# POWER.net
KiCad netlist of a schematic drawn in Altium Designer
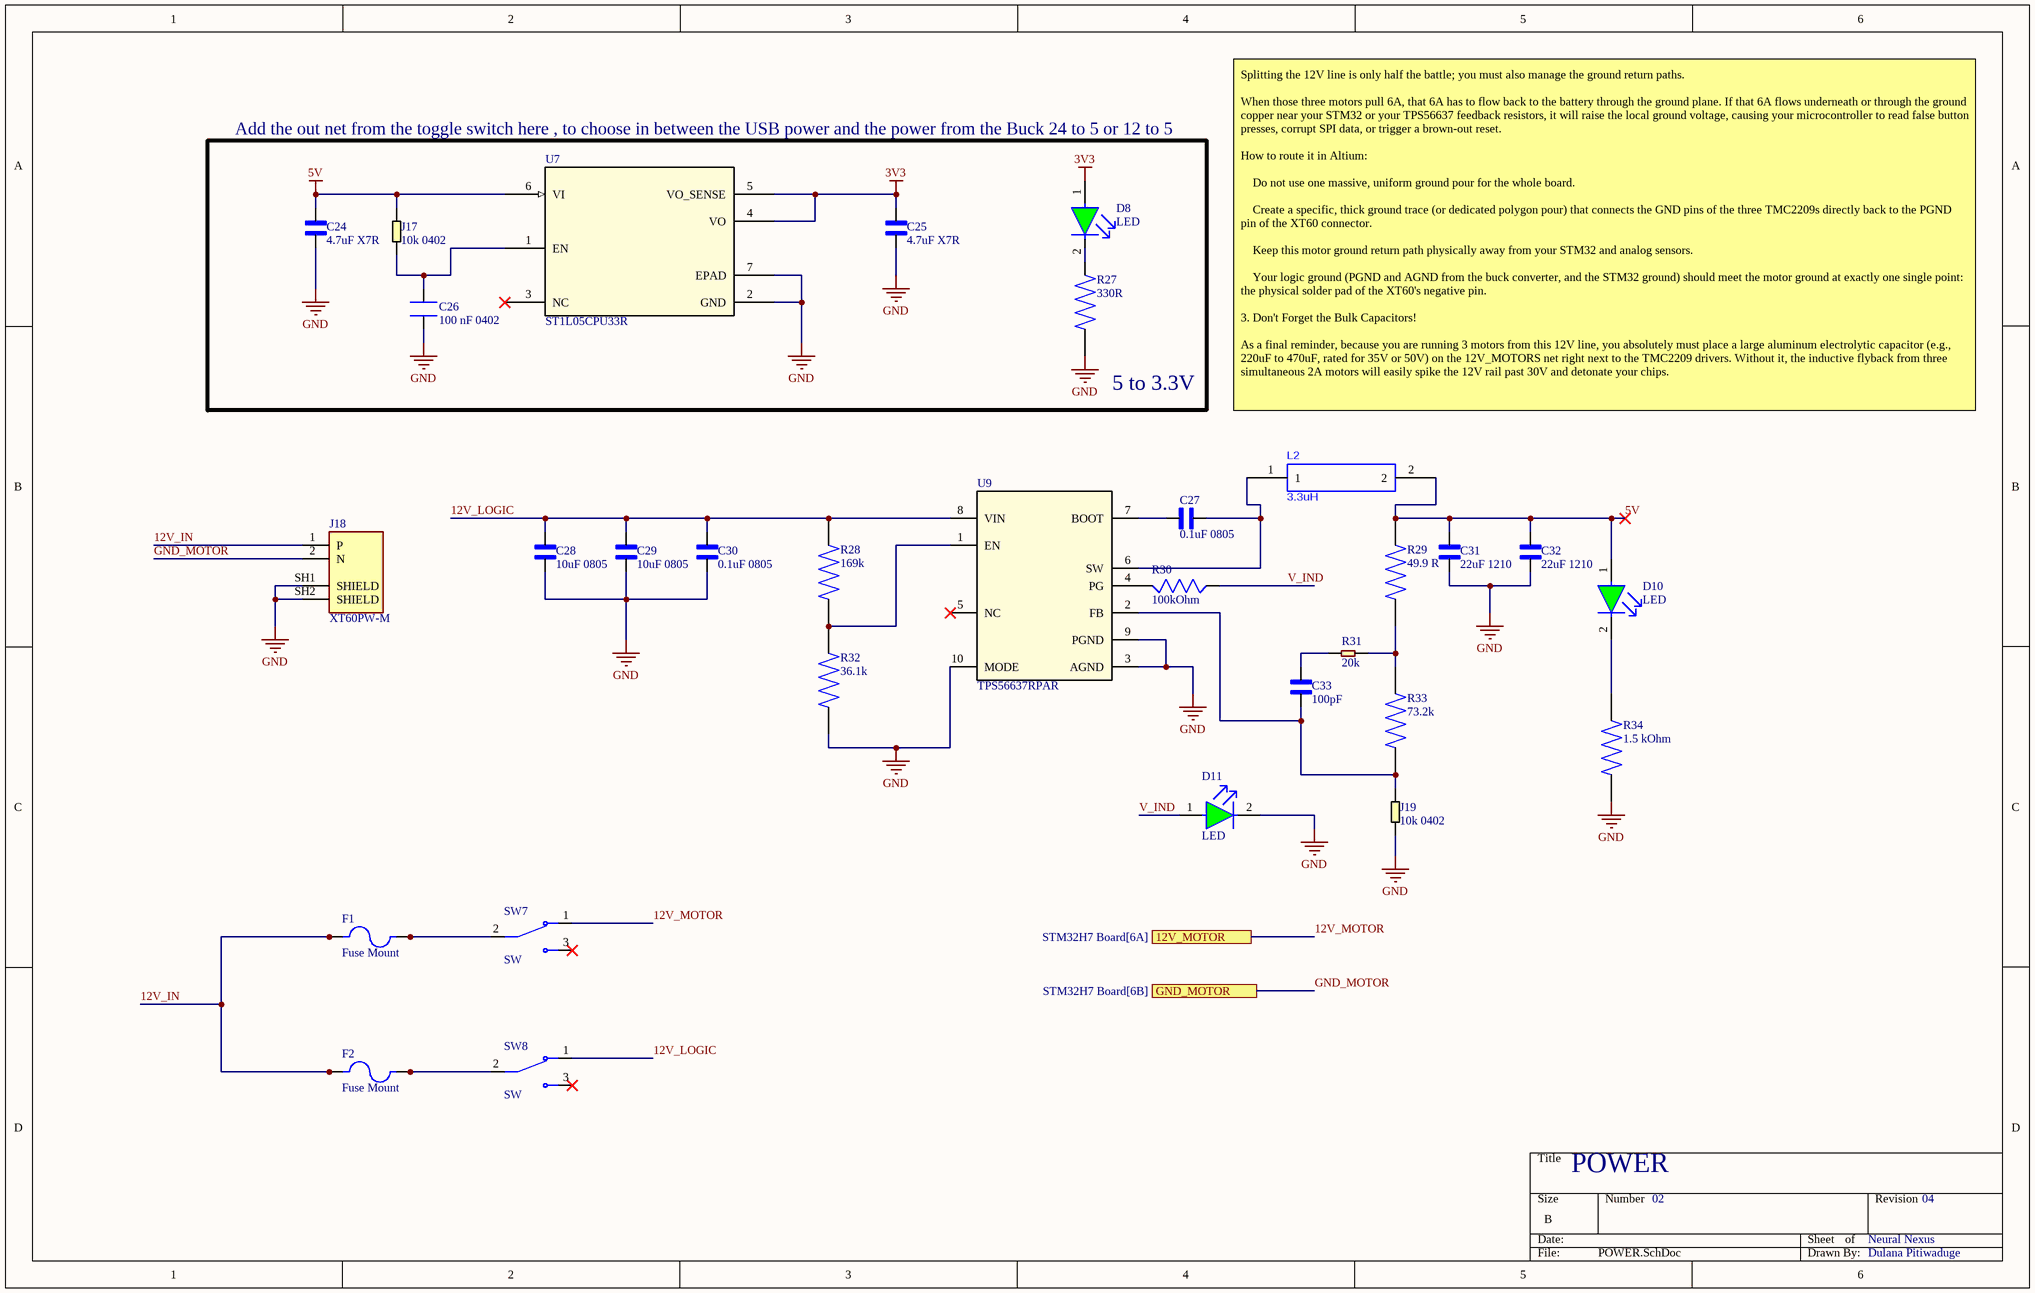
[diagram p0: POWER.SchDoc]

(export (version "E")
  (design (tool "Eeschema 10.0.6"))
  (components
    (comp (ref "C24")
      (value "4.7uF X7R")
      (footprint "CAPC2012X145N")
      (description "C Series 0805 4.7 uF 10 V Â±10% Tolerance X7R SMT Multilayer Ceramic Capacitor")
      (fields (field (name "MF") "TDK") (field (name "MP") "C2012X7R1A475K125AC"))
      (libsource (lib "Schlib1") (part "C2012X7R1A475K125AC"))
    )
    (comp (ref "C25")
      (value "4.7uF X7R")
      (footprint "CAPC2012X145N")
      (description "C Series 0805 4.7 uF 10 V Â±10% Tolerance X7R SMT Multilayer Ceramic Capacitor")
      (fields (field (name "MF") "TDK") (field (name "MP") "C2012X7R1A475K125AC"))
      (libsource (lib "Schlib1") (part "C2012X7R1A475K125AC"))
    )
    (comp (ref "C26")
      (value "100 nF 0402")
      (footprint "CAPC1005X55N")
      (description "0.1 ÂµF Â±10% 10V Ceramic Capacitor X7R 0402 (1005 Metric)")
      (fields (field (name "MF") "Samsung Electro-Mechanics") (field (name "MP") "CL05B104KP5NNNC"))
      (libsource (lib "EDR") (part "CL05B104KP5NNNC"))
    )
    (comp (ref "C27")
      (value "0.1uF 0805")
      (footprint "CAPC2012X95N")
      (description "0.1 ÂµF Â±10% 50V Ceramic Capacitor X7R 0805 (2012 Metric)")
      (fields (field (name "MF") "Samsung Electro-Mechanics") (field (name "MP") "CL21B104KBCNNNC"))
      (libsource (lib "Schlib1") (part "CL21B104KBCNNNC"))
    )
    (comp (ref "C28")
      (value "10uF 0805")
      (footprint "CAPC2012X145N")
      (description "SMD capacitor X7R(MURATA) with capacitance 10uF Tol.10%. Rated voltage 25Vdc 125C")
      (fields (field (name "MF") "Murata") (field (name "MP") "GRM21BZ71E106KE15L"))
      (libsource (lib "Schlib1") (part "GRM21BZ71E106KE15L"))
    )
    (comp (ref "C29")
      (value "10uF 0805")
      (footprint "CAPC2012X145N")
      (description "SMD capacitor X7R(MURATA) with capacitance 10uF Tol.10%. Rated voltage 25Vdc 125C")
      (fields (field (name "MF") "Murata") (field (name "MP") "GRM21BZ71E106KE15L"))
      (libsource (lib "Schlib1") (part "GRM21BZ71E106KE15L"))
    )
    (comp (ref "C30")
      (value "0.1uF 0805")
      (footprint "CAPC2012X95N")
      (description "0.1 ÂµF Â±10% 50V Ceramic Capacitor X7R 0805 (2012 Metric)")
      (fields (field (name "MF") "Samsung Electro-Mechanics") (field (name "MP") "CL21B104KBCNNNC"))
      (libsource (lib "") (part "CL21B104KBCNNNC_1"))
    )
    (comp (ref "C31")
      (value "22uF 1210")
      (footprint "CAPC3225X270N")
      (description "SMD capacitor X7R(EIA) with capacitance 22uF Tol.10%. Rated voltage 25Vdc 125C")
      (fields (field (name "MF") "Murata Electronics") (field (name "MP") "GRM32ER71E226KE15L"))
      (libsource (lib "Schlib1") (part "GRM32ER71E226KE15L"))
    )
    (comp (ref "C32")
      (value "22uF 1210")
      (footprint "CAPC3225X270N")
      (description "SMD capacitor X7R(EIA) with capacitance 22uF Tol.10%. Rated voltage 25Vdc 125C")
      (fields (field (name "MF") "Murata Electronics") (field (name "MP") "GRM32ER71E226KE15L"))
      (libsource (lib "Schlib1") (part "GRM32ER71E226KE15L"))
    )
    (comp (ref "C33")
      (value "100pF")
      (footprint "CAPC1005X55N")
      (description "100 pF Â±5% 50V Ceramic Capacitor C0G, NP0 0402 (1005 Metric)")
      (fields (field (name "MF") "Samsung Electro-Mechanics") (field (name "MP") "CL05C101JB5NNNC"))
      (libsource (lib "EDR") (part "CL05C101JB5NNNC"))
    )
    (comp (ref "D8")
      (value "LED")
      (footprint "FP-SML-LX0805SRC-TR-MFG")
      (description "LED RED CLEAR SMD")
      (fields (field (name "TRONIC PART NO") "LE0011"))
      (libsource (lib "EDR") (part "RED GREEN"))
    )
    (comp (ref "D10")
      (value "LED")
      (footprint "FP-SML-LX0805SRC-TR-MFG")
      (description "LED RED CLEAR SMD")
      (fields (field (name "TRONIC PART NO") "LE0011"))
      (libsource (lib "EDR") (part "RED GREEN"))
    )
    (comp (ref "D11")
      (value "LED")
      (footprint "FP-SML-LX0805SRC-TR-MFG")
      (description "LED RED CLEAR SMD")
      (fields (field (name "TRONIC PART NO") "LE0011"))
      (libsource (lib "EDR") (part "RED GREEN"))
    )
    (comp (ref "F1")
      (value "Fuse Mount")
      (footprint "FUSE_3568")
      (fields (field (name "MF") "Keystone Electronics") (field (name "MP") "3568"))
      (libsource (lib "EDR") (part "Fuse Mount"))
    )
    (comp (ref "F2")
      (value "Fuse Mount")
      (footprint "FUSE_3568")
      (fields (field (name "MF") "Keystone Electronics") (field (name "MP") "3568"))
      (libsource (lib "EDR") (part "Fuse Mount"))
    )
    (comp (ref "J17")
      (value "10k 0402")
      (footprint "RESC1005X40N")
      (description "301010004")
      (fields (field (name "MF") "{'manufacturer': u'YAGEO'}") (field (name "MP") "RC0402JR-0710KL"))
      (libsource (lib "EDR") (part "SMD-RES-10K-5%-1/(0402)"))
    )
    (comp (ref "J18")
      (value "XT60PW-M")
      (footprint "AMASS_XT60PW-M")
      (description "Socket, DC supply, male, PIN: 2")
      (fields (field (name "MF") "AMASS") (field (name "LCSC PART NUMBER") "C98732"))
      (libsource (lib "EDR") (part "XT60PW-M"))
    )
    (comp (ref "J19")
      (value "10k 0402")
      (footprint "RESC1005X40N")
      (description "301010004")
      (fields (field (name "MF") "{'manufacturer': u'YAGEO'}") (field (name "MP") "RC0402JR-0710KL"))
      (libsource (lib "EDR") (part "SMD-RES-10K-5%-1/(0402)"))
    )
    (comp (ref "L2")
      (value "3.3uH")
      (footprint "IND-SMD_L4.0-W4.0 - duplicate")
      (description "FHD4020S-3R3MT")
      (fields (field (name "TRONIC PART NO") "IN0008"))
      (libsource (lib "EDR") (part "33uH"))
    )
    (comp (ref "R27")
      (value "330R")
      (footprint "RESC1005X40N")
      (description "330 Ohms Â±1% 0.063W, 1/16W Chip Resistor 0402 (1005 Metric) Moisture Resistant Thick Film")
      (fields (field (name "MF") "Yageo") (field (name "MP") "RC0402FR-07330RL"))
      (libsource (lib "EDR") (part "RC0402FR-07330RL"))
    )
    (comp (ref "R28")
      (value "169k")
      (footprint "RESC1508X55N")
      (description "169 kOhms Â±1% 0.1W, 1/10W Chip Resistor 0603 (1608 Metric) Automotive AEC-Q200 Thick Film")
      (fields (field (name "MF") "Stackpole Electronics Inc") (field (name "MP") "RMCF0603FT169K"))
      (libsource (lib "EDR") (part "RMCF0603FT169K"))
    )
    (comp (ref "R29")
      (value "49.9 R")
      (footprint "RESC1005X40N")
      (fields (field (name "MF") "Vishay Dale") (field (name "MP") "CRCW040249R9FKED"))
      (libsource (lib "EDR") (part "CRCW040249R9FKED"))
    )
    (comp (ref "R30")
      (value "100kOhm")
      (footprint "RESC1005X40")
      (description "100 kOhms Â±1% 0.063W, 1/16W Chip Resistor 0402 (1005 Metric) Moisture Resistant Thick Film")
      (fields (field (name "MF") "Yageo") (field (name "MP") "RC0402FR-07100KL"))
      (libsource (lib "EDR") (part "RC0402FR-07100KL"))
    )
    (comp (ref "R31")
      (value "20k")
      (footprint "R0603")
      (description "20 kOhms Â±1% 0.1W, 1/10W Chip Resistor 0603 (1608 Metric) Moisture Resistant Thick Film")
      (fields (field (name "MF") "Yageo") (field (name "MP") "RC0603FR-0720KL"))
      (libsource (lib "EDR") (part "SMD-RES-20K-1%-1/10W(0603)"))
    )
    (comp (ref "R32")
      (value "36.1k")
      (footprint "RESC1608X55N")
      (description "RES SMD 36.1KOHM 0.1% 1/10W 0603")
      (fields (field (name "MF") "{'manufacturer': u'YAGEO'}") (field (name "MP") "RT0603BRD0736K1L"))
      (libsource (lib "EDR") (part "RT0603BRD0736K1L"))
    )
    (comp (ref "R33")
      (value "73.2k")
      (footprint "RESC1005X35N")
      (description "RES 73.2K OHM 1% 1/16W 0402")
      (fields (field (name "MP") "RMCF0402FT73K2"))
      (libsource (lib "EDR") (part "RMCF0402FT73K2"))
    )
    (comp (ref "R34")
      (value "1.5 kOhm")
      (footprint "RESC1005X40N")
      (description "1.5 kOhms Â±1% 0.063W, 1/16W Chip Resistor 0402 (1005 Metric) Moisture Resistant Thick Film")
      (fields (field (name "MF") "Yageo") (field (name "MP") "RC0402FR-071K5L"))
      (libsource (lib "EDR") (part "RC0402FR-071K5L"))
    )
    (comp (ref "SW7")
      (value "SW")
      (footprint "SW_100SP3T1B1M2QE")
      (description "TOGGLE, 5A, 120VAC/28VDC SPDT, On-Off-On, Panel Mount, Through Hole")
      (fields (field (name "MF") "E-Switch") (field (name "MP") "100SP3T1B1M2QE"))
      (libsource (lib "EDR") (part "100SP3T1B1M2QE"))
    )
    (comp (ref "SW8")
      (value "SW")
      (footprint "SW_100SP3T1B1M2QE")
      (description "TOGGLE, 5A, 120VAC/28VDC SPDT, On-Off-On, Panel Mount, Through Hole")
      (fields (field (name "MF") "E-Switch") (field (name "MP") "100SP3T1B1M2QE"))
      (libsource (lib "EDR") (part "100SP3T1B1M2QE"))
    )
    (comp (ref "U7")
      (value "ST1L05CPU33R")
      (footprint "DFN6_3X3_STM")
      (description "Very low quiescent BiCMOS voltage regulator")
      (fields (field (name "COPYRIGHT") "Copyright (C) 2026 Ultra Librarian. All rights reserved."))
      (libsource (lib "Schlib1") (part "ST1L05CPU33R"))
    )
    (comp (ref "U9")
      (value "TPS56637RPAR")
      (footprint "CONV_TPS56637RPAR")
      (description "4.5-V to 28-V, 6-A synchronous buck converter with ULQ-Mode 10-VQFN-HR -40 to 150")
      (fields (field (name "COPYRIGHT") "Copyright (C) 2026 Ultra Librarian. All rights reserved."))
      (libsource (lib "Schlib1") (part "TPS56637RPAR"))
    )
  )
  (nets
    (net (code "1") (name "/12V_IN") (class "Default")
      (node (ref "F1") (pin "1") (pinfunction "1_1") (pintype "passive"))
      (node (ref "F1") (pin "3") (pinfunction "1_3") (pintype "passive"))
      (node (ref "F2") (pin "1") (pinfunction "1_1") (pintype "passive"))
      (node (ref "F2") (pin "3") (pinfunction "1_3") (pintype "passive"))
      (node (ref "J18") (pin "1") (pinfunction "P_1") (pintype "passive"))
    )
    (net (code "2") (name "/12V_LOGIC") (class "Default")
      (node (ref "C28") (pin "2") (pinfunction "2_2") (pintype "passive"))
      (node (ref "C29") (pin "2") (pinfunction "2_2") (pintype "passive"))
      (node (ref "C30") (pin "2") (pinfunction "2_2") (pintype "passive"))
      (node (ref "R28") (pin "2") (pinfunction "2_2") (pintype "passive"))
      (node (ref "SW8") (pin "1") (pinfunction "1_1") (pintype "passive"))
      (node (ref "U9") (pin "8") (pinfunction "VIN_8") (pintype "power_in"))
    )
    (net (code "3") (name "/12V_MOTOR") (class "Default")
      (node (ref "SW7") (pin "1") (pinfunction "1_1") (pintype "passive"))
    )
    (net (code "4") (name "/GND_MOTOR") (class "Default")
      (node (ref "J18") (pin "2") (pinfunction "N_2") (pintype "passive"))
    )
    (net (code "5") (name "/V_IND") (class "Default")
      (node (ref "D11") (pin "1") (pinfunction "A_1") (pintype "passive"))
      (node (ref "R30") (pin "2") (pinfunction "2_2") (pintype "passive"))
    )
    (net (code "6") (name "3V3") (class "Default")
      (node (ref "C25") (pin "2") (pinfunction "2_2") (pintype "passive"))
      (node (ref "D8") (pin "1") (pinfunction "A_1") (pintype "passive"))
      (node (ref "U7") (pin "4") (pinfunction "VO_4") (pintype "passive"))
      (node (ref "U7") (pin "5") (pinfunction "VO_SENSE_5") (pintype "passive"))
    )
    (net (code "7") (name "5V") (class "Default")
      (node (ref "C24") (pin "2") (pinfunction "2_2") (pintype "passive"))
      (node (ref "C31") (pin "2") (pinfunction "2_2") (pintype "passive"))
      (node (ref "C32") (pin "2") (pinfunction "2_2") (pintype "passive"))
      (node (ref "D10") (pin "1") (pinfunction "A_1") (pintype "passive"))
      (node (ref "J17") (pin "2") (pinfunction "2_2") (pintype "passive"))
      (node (ref "L2") (pin "2") (pinfunction "2_2") (pintype "passive"))
      (node (ref "R29") (pin "2") (pinfunction "2_2") (pintype "passive"))
      (node (ref "U7") (pin "6") (pinfunction "VI_6") (pintype "input"))
    )
    (net (code "8") (name "GND") (class "Default")
      (node (ref "C24") (pin "1") (pinfunction "1_1") (pintype "passive"))
      (node (ref "C25") (pin "1") (pinfunction "1_1") (pintype "passive"))
      (node (ref "C26") (pin "1") (pinfunction "1_1") (pintype "passive"))
      (node (ref "C28") (pin "1") (pinfunction "1_1") (pintype "passive"))
      (node (ref "C29") (pin "1") (pinfunction "1_1") (pintype "passive"))
      (node (ref "C30") (pin "1") (pinfunction "1_1") (pintype "passive"))
      (node (ref "C31") (pin "1") (pinfunction "1_1") (pintype "passive"))
      (node (ref "C32") (pin "1") (pinfunction "1_1") (pintype "passive"))
      (node (ref "D11") (pin "2") (pinfunction "C_2") (pintype "passive"))
      (node (ref "J18") (pin "SH1") (pinfunction "SHIELD_SH1") (pintype "passive"))
      (node (ref "J18") (pin "SH2") (pinfunction "SHIELD_SH2") (pintype "passive"))
      (node (ref "J19") (pin "1") (pinfunction "1_1") (pintype "passive"))
      (node (ref "R27") (pin "1") (pinfunction "1_1") (pintype "passive"))
      (node (ref "R32") (pin "1") (pinfunction "1_1") (pintype "passive"))
      (node (ref "R34") (pin "1") (pinfunction "1_1") (pintype "passive"))
      (node (ref "U7") (pin "2") (pinfunction "GND_2") (pintype "power_in"))
      (node (ref "U7") (pin "7") (pinfunction "EPAD_7") (pintype "passive"))
      (node (ref "U9") (pin "10") (pinfunction "MODE_10") (pintype "power_in"))
      (node (ref "U9") (pin "3") (pinfunction "AGND_3") (pintype "power_in"))
      (node (ref "U9") (pin "9") (pinfunction "PGND_9") (pintype "power_in"))
    )
    (net (code "9") (name "Net-(C33-Pad2)") (class "Default")
      (node (ref "C33") (pin "2") (pinfunction "2_2") (pintype "passive"))
      (node (ref "R31") (pin "1") (pinfunction "1_1") (pintype "passive"))
    )
    (net (code "10") (name "Net-(D8-C)") (class "Default")
      (node (ref "D8") (pin "2") (pinfunction "C_2") (pintype "passive"))
      (node (ref "R27") (pin "2") (pinfunction "2_2") (pintype "passive"))
    )
    (net (code "11") (name "Net-(D10-C)") (class "Default")
      (node (ref "D10") (pin "2") (pinfunction "C_2") (pintype "passive"))
      (node (ref "R34") (pin "2") (pinfunction "2_2") (pintype "passive"))
    )
    (net (code "12") (name "Net-(F1-2-Pad4)") (class "Default")
      (node (ref "F1") (pin "2") (pinfunction "2_2") (pintype "passive"))
      (node (ref "F1") (pin "4") (pinfunction "2_4") (pintype "passive"))
      (node (ref "SW7") (pin "2") (pinfunction "2_2") (pintype "passive"))
    )
    (net (code "13") (name "Net-(F2-2-Pad4)") (class "Default")
      (node (ref "F2") (pin "2") (pinfunction "2_2") (pintype "passive"))
      (node (ref "F2") (pin "4") (pinfunction "2_4") (pintype "passive"))
      (node (ref "SW8") (pin "2") (pinfunction "2_2") (pintype "passive"))
    )
    (net (code "14") (name "Net-(R29-Pad1)") (class "Default")
      (node (ref "R29") (pin "1") (pinfunction "1_1") (pintype "passive"))
      (node (ref "R31") (pin "2") (pinfunction "2_2") (pintype "passive"))
      (node (ref "R33") (pin "2") (pinfunction "2_2") (pintype "passive"))
    )
    (net (code "15") (name "Net-(U7-EN)") (class "Default")
      (node (ref "C26") (pin "2") (pinfunction "2_2") (pintype "passive"))
      (node (ref "J17") (pin "1") (pinfunction "1_1") (pintype "passive"))
      (node (ref "U7") (pin "1") (pinfunction "EN_1") (pintype "passive"))
    )
    (net (code "16") (name "Net-(U9-BOOT)") (class "Default")
      (node (ref "C27") (pin "2") (pinfunction "2_2") (pintype "passive"))
      (node (ref "U9") (pin "7") (pinfunction "BOOT_7") (pintype "power_in"))
    )
    (net (code "17") (name "Net-(U9-EN)") (class "Default")
      (node (ref "R28") (pin "1") (pinfunction "1_1") (pintype "passive"))
      (node (ref "R32") (pin "2") (pinfunction "2_2") (pintype "passive"))
      (node (ref "U9") (pin "1") (pinfunction "EN_1") (pintype "power_in"))
    )
    (net (code "18") (name "Net-(U9-FB)") (class "Default")
      (node (ref "C33") (pin "1") (pinfunction "1_1") (pintype "passive"))
      (node (ref "J19") (pin "2") (pinfunction "2_2") (pintype "passive"))
      (node (ref "R33") (pin "1") (pinfunction "1_1") (pintype "passive"))
      (node (ref "U9") (pin "2") (pinfunction "FB_2") (pintype "power_in"))
    )
    (net (code "19") (name "Net-(U9-PG)") (class "Default")
      (node (ref "R30") (pin "1") (pinfunction "1_1") (pintype "passive"))
      (node (ref "U9") (pin "4") (pinfunction "PG_4") (pintype "power_in"))
    )
    (net (code "20") (name "Net-(U9-SW)") (class "Default")
      (node (ref "C27") (pin "1") (pinfunction "1_1") (pintype "passive"))
      (node (ref "L2") (pin "1") (pinfunction "1_1") (pintype "passive"))
      (node (ref "U9") (pin "6") (pinfunction "SW_6") (pintype "power_in"))
    )
    (net (code "21") (name "unconnected-(SW7-Pad3)") (class "Default")
      (node (ref "SW7") (pin "3") (pinfunction "3_3") (pintype "passive+no_connect"))
    )
    (net (code "22") (name "unconnected-(SW8-Pad3)") (class "Default")
      (node (ref "SW8") (pin "3") (pinfunction "3_3") (pintype "passive+no_connect"))
    )
    (net (code "23") (name "unconnected-(U7-NC-Pad3)") (class "Default")
      (node (ref "U7") (pin "3") (pinfunction "NC_3") (pintype "passive+no_connect"))
    )
    (net (code "24") (name "unconnected-(U9-NC-Pad5)") (class "Default")
      (node (ref "U9") (pin "5") (pinfunction "NC_5") (pintype "passive+no_connect"))
    )
  )
)
